# SPIDER_ROBOT.net
KiCad netlist of a schematic drawn in Altium Designer
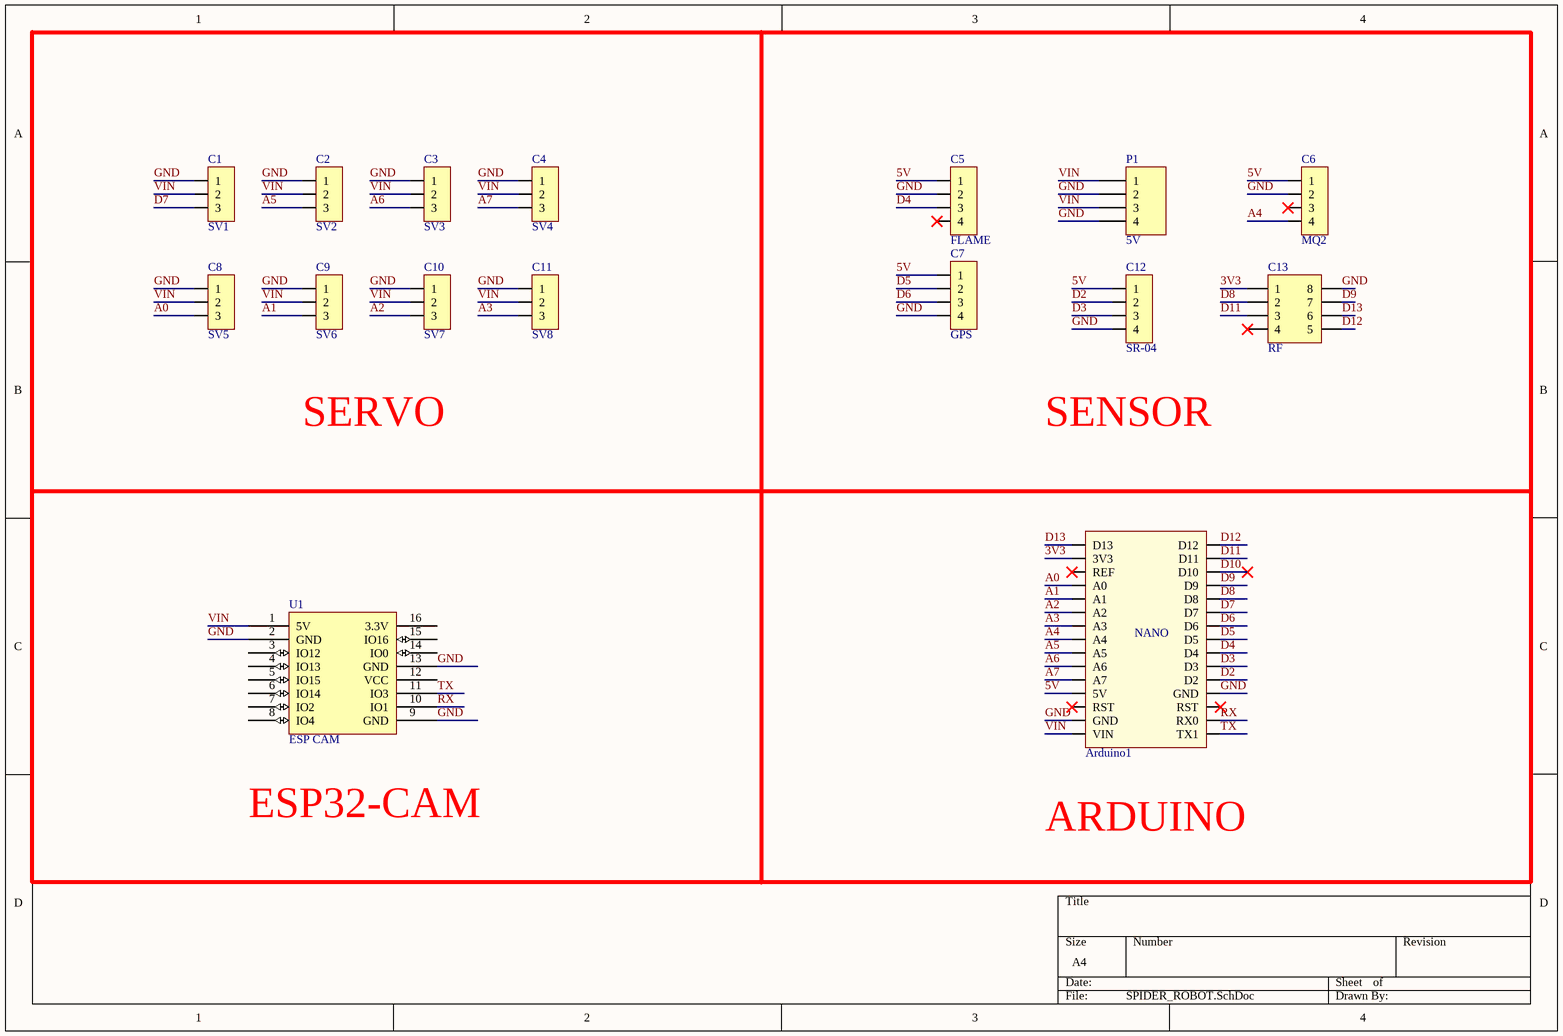
[diagram p0: SPIDER_ROBOT.SchDoc]

(export (version "E")
  (design (tool "Eeschema 10.0.6"))
  (components
    (comp (ref "Arduino1")
      (value "Arduino Nano")
      (footprint "Arduino Nano")
      (description "Arduino NANO")
      (libsource (lib "[Eryson]_Library") (part "Arduino Nano"))
    )
    (comp (ref "C1")
      (value "SV1")
      (footprint "JP3-D1T")
      (description "WR-PHD 2.54 mm Angled Socket Header")
      (fields
        (field (name "MANUFACTURER") "Würth Elektronik eiSos GmbH")
        (field (name "PARTNO") "613003143121")
        (field (name "CREATED BY") "Karrer Zheng")
      )
      (libsource (lib "[Eryson]_Library") (part "JP3"))
    )
    (comp (ref "C2")
      (value "SV2")
      (footprint "JP3-D1T")
      (description "WR-PHD 2.54 mm Angled Socket Header")
      (fields
        (field (name "MANUFACTURER") "Würth Elektronik eiSos GmbH")
        (field (name "PARTNO") "613003143121")
        (field (name "CREATED BY") "Karrer Zheng")
      )
      (libsource (lib "[Eryson]_Library") (part "JP3"))
    )
    (comp (ref "C3")
      (value "SV3")
      (footprint "JP3-D1T")
      (description "WR-PHD 2.54 mm Angled Socket Header")
      (fields
        (field (name "MANUFACTURER") "Würth Elektronik eiSos GmbH")
        (field (name "PARTNO") "613003143121")
        (field (name "CREATED BY") "Karrer Zheng")
      )
      (libsource (lib "[Eryson]_Library") (part "JP3"))
    )
    (comp (ref "C4")
      (value "SV4")
      (footprint "JP3-D1T")
      (description "WR-PHD 2.54 mm Angled Socket Header")
      (fields
        (field (name "MANUFACTURER") "Würth Elektronik eiSos GmbH")
        (field (name "PARTNO") "613003143121")
        (field (name "CREATED BY") "Karrer Zheng")
      )
      (libsource (lib "[Eryson]_Library") (part "JP3"))
    )
    (comp (ref "C5")
      (value "FLAME")
      (footprint "JP4-C1T")
      (description "WR-PHD 2.54 mm Angled Socket Header")
      (fields
        (field (name "MANUFACTURER") "Würth Elektronik eiSos GmbH")
        (field (name "PARTNO") "613004143121")
        (field (name "CREATED BY") "Karrer Zheng")
      )
      (libsource (lib "[Eryson]_Library") (part "JP4"))
    )
    (comp (ref "C6")
      (value "MQ2")
      (footprint "JP4-C1T")
      (description "WR-PHD 2.54 mm Angled Socket Header")
      (fields
        (field (name "MANUFACTURER") "Würth Elektronik eiSos GmbH")
        (field (name "PARTNO") "613004143121")
        (field (name "CREATED BY") "Karrer Zheng")
      )
      (libsource (lib "[Eryson]_Library") (part "JP4"))
    )
    (comp (ref "C7")
      (value "GPS")
      (footprint "JP4-C1T")
      (description "WR-PHD 2.54 mm Angled Socket Header")
      (fields
        (field (name "MANUFACTURER") "Würth Elektronik eiSos GmbH")
        (field (name "PARTNO") "613004143121")
        (field (name "CREATED BY") "Karrer Zheng")
      )
      (libsource (lib "[Eryson]_Library") (part "JP4"))
    )
    (comp (ref "C8")
      (value "SV5")
      (footprint "JP3-D1T")
      (description "WR-PHD 2.54 mm Angled Socket Header")
      (fields
        (field (name "MANUFACTURER") "Würth Elektronik eiSos GmbH")
        (field (name "PARTNO") "613003143121")
        (field (name "CREATED BY") "Karrer Zheng")
      )
      (libsource (lib "[Eryson]_Library") (part "JP3"))
    )
    (comp (ref "C9")
      (value "SV6")
      (footprint "JP3-D1T")
      (description "WR-PHD 2.54 mm Angled Socket Header")
      (fields
        (field (name "MANUFACTURER") "Würth Elektronik eiSos GmbH")
        (field (name "PARTNO") "613003143121")
        (field (name "CREATED BY") "Karrer Zheng")
      )
      (libsource (lib "[Eryson]_Library") (part "JP3"))
    )
    (comp (ref "C10")
      (value "SV7")
      (footprint "JP3-D1T")
      (description "WR-PHD 2.54 mm Angled Socket Header")
      (fields
        (field (name "MANUFACTURER") "Würth Elektronik eiSos GmbH")
        (field (name "PARTNO") "613003143121")
        (field (name "CREATED BY") "Karrer Zheng")
      )
      (libsource (lib "[Eryson]_Library") (part "JP3"))
    )
    (comp (ref "C11")
      (value "SV8")
      (footprint "JP3-D1T")
      (description "WR-PHD 2.54 mm Angled Socket Header")
      (fields
        (field (name "MANUFACTURER") "Würth Elektronik eiSos GmbH")
        (field (name "PARTNO") "613003143121")
        (field (name "CREATED BY") "Karrer Zheng")
      )
      (libsource (lib "[Eryson]_Library") (part "JP3"))
    )
    (comp (ref "C12")
      (value "SR-04")
      (footprint "JP4-C1T")
      (description "WR-PHD 2.54 mm Angled Socket Header")
      (fields
        (field (name "MANUFACTURER") "Würth Elektronik eiSos GmbH")
        (field (name "PARTNO") "613004143121")
        (field (name "CREATED BY") "Karrer Zheng")
      )
      (libsource (lib "[Eryson]_Library") (part "JP4"))
    )
    (comp (ref "C13")
      (value "RF")
      (footprint "JP4-C2T")
      (description "WR-PHD 2.54 mm Dual Socket Header")
      (fields
        (field (name "MANUFACTURER") "Würth Elektronik eiSos GmbH")
        (field (name "PARTNO") "61300821821")
        (field (name "CREATED BY") "Karrer Zheng")
      )
      (libsource (lib "[Eryson]_Library") (part "JP4x2"))
    )
    (comp (ref "P1")
      (value "5V")
      (footprint "DOMINO_4P_2.54MM")
      (libsource (lib "[Eryson]_Library") (part "Domino 4 pin"))
    )
    (comp (ref "U1")
      (value "ESP CAM")
      (footprint "ESP32_CAM")
      (description "ESP-12 Wi-Fi Module by AI-Thinker")
      (libsource (lib "[Eryson]_Library") (part "ESP32_CAM"))
    )
  )
  (nets
    (net (code "1") (name "/3V3") (class "Default")
      (node (ref "Arduino1") (pin "3V3") (pinfunction "3V3_3V3") (pintype "passive"))
      (node (ref "C13") (pin "1") (pinfunction "1_1") (pintype "passive"))
    )
    (net (code "2") (name "/5V") (class "Default")
      (node (ref "Arduino1") (pin "5V") (pinfunction "5V_5V") (pintype "passive"))
      (node (ref "C12") (pin "1") (pinfunction "1_1") (pintype "passive"))
      (node (ref "C5") (pin "1") (pinfunction "1_1") (pintype "passive"))
      (node (ref "C6") (pin "1") (pinfunction "1_1") (pintype "passive"))
      (node (ref "C7") (pin "1") (pinfunction "1_1") (pintype "passive"))
    )
    (net (code "3") (name "/A0") (class "Default")
      (node (ref "Arduino1") (pin "A0") (pinfunction "A0_A0") (pintype "passive"))
      (node (ref "C8") (pin "3") (pinfunction "3_3") (pintype "passive"))
    )
    (net (code "4") (name "/A1") (class "Default")
      (node (ref "Arduino1") (pin "A1") (pinfunction "A1_A1") (pintype "passive"))
      (node (ref "C9") (pin "3") (pinfunction "3_3") (pintype "passive"))
    )
    (net (code "5") (name "/A2") (class "Default")
      (node (ref "Arduino1") (pin "A2") (pinfunction "A2_A2") (pintype "passive"))
      (node (ref "C10") (pin "3") (pinfunction "3_3") (pintype "passive"))
    )
    (net (code "6") (name "/A3") (class "Default")
      (node (ref "Arduino1") (pin "A3") (pinfunction "A3_A3") (pintype "passive"))
      (node (ref "C11") (pin "3") (pinfunction "3_3") (pintype "passive"))
    )
    (net (code "7") (name "/A4") (class "Default")
      (node (ref "Arduino1") (pin "A4") (pinfunction "A4_A4") (pintype "passive"))
      (node (ref "C6") (pin "4") (pinfunction "4_4") (pintype "passive"))
    )
    (net (code "8") (name "/A5") (class "Default")
      (node (ref "Arduino1") (pin "A5") (pinfunction "A5_A5") (pintype "passive"))
      (node (ref "C2") (pin "3") (pinfunction "3_3") (pintype "passive"))
    )
    (net (code "9") (name "/A6") (class "Default")
      (node (ref "Arduino1") (pin "A6") (pinfunction "A6_A6") (pintype "passive"))
      (node (ref "C3") (pin "3") (pinfunction "3_3") (pintype "passive"))
    )
    (net (code "10") (name "/A7") (class "Default")
      (node (ref "Arduino1") (pin "A7") (pinfunction "A7_A7") (pintype "passive"))
      (node (ref "C4") (pin "3") (pinfunction "3_3") (pintype "passive"))
    )
    (net (code "11") (name "/D2") (class "Default")
      (node (ref "Arduino1") (pin "D2") (pinfunction "D2_D2") (pintype "passive"))
      (node (ref "C12") (pin "2") (pinfunction "2_2") (pintype "passive"))
    )
    (net (code "12") (name "/D3") (class "Default")
      (node (ref "Arduino1") (pin "D3") (pinfunction "D3_D3") (pintype "passive"))
      (node (ref "C12") (pin "3") (pinfunction "3_3") (pintype "passive"))
    )
    (net (code "13") (name "/D4") (class "Default")
      (node (ref "Arduino1") (pin "D4") (pinfunction "D4_D4") (pintype "passive"))
      (node (ref "C5") (pin "3") (pinfunction "3_3") (pintype "passive"))
    )
    (net (code "14") (name "/D5") (class "Default")
      (node (ref "Arduino1") (pin "D5") (pinfunction "D5_D5") (pintype "passive"))
      (node (ref "C7") (pin "2") (pinfunction "2_2") (pintype "passive"))
    )
    (net (code "15") (name "/D6") (class "Default")
      (node (ref "Arduino1") (pin "D6") (pinfunction "D6_D6") (pintype "passive"))
      (node (ref "C7") (pin "3") (pinfunction "3_3") (pintype "passive"))
    )
    (net (code "16") (name "/D7") (class "Default")
      (node (ref "Arduino1") (pin "D7") (pinfunction "D7_D7") (pintype "passive"))
      (node (ref "C1") (pin "3") (pinfunction "3_3") (pintype "passive"))
    )
    (net (code "17") (name "/D8") (class "Default")
      (node (ref "Arduino1") (pin "D8") (pinfunction "D8_D8") (pintype "passive"))
      (node (ref "C13") (pin "2") (pinfunction "2_2") (pintype "passive"))
    )
    (net (code "18") (name "/D9") (class "Default")
      (node (ref "Arduino1") (pin "D9") (pinfunction "D9_D9") (pintype "passive"))
      (node (ref "C13") (pin "7") (pinfunction "7_7") (pintype "passive"))
    )
    (net (code "19") (name "/D10") (class "Default")
      (node (ref "Arduino1") (pin "D10") (pinfunction "D10_D10") (pintype "passive+no_connect"))
    )
    (net (code "20") (name "/D11") (class "Default")
      (node (ref "Arduino1") (pin "D11") (pinfunction "D11_D11") (pintype "passive"))
      (node (ref "C13") (pin "3") (pinfunction "3_3") (pintype "passive"))
    )
    (net (code "21") (name "/D12") (class "Default")
      (node (ref "Arduino1") (pin "D12") (pinfunction "D12_D12") (pintype "passive"))
      (node (ref "C13") (pin "5") (pinfunction "5_5") (pintype "passive"))
    )
    (net (code "22") (name "/D13") (class "Default")
      (node (ref "Arduino1") (pin "D13") (pinfunction "D13_D13") (pintype "passive"))
      (node (ref "C13") (pin "6") (pinfunction "6_6") (pintype "passive"))
    )
    (net (code "23") (name "/GND") (class "Default")
      (node (ref "Arduino1") (pin "GND") (pinfunction "GND_GND") (pintype "passive"))
      (node (ref "C1") (pin "1") (pinfunction "1_1") (pintype "passive"))
      (node (ref "C10") (pin "1") (pinfunction "1_1") (pintype "passive"))
      (node (ref "C11") (pin "1") (pinfunction "1_1") (pintype "passive"))
      (node (ref "C12") (pin "4") (pinfunction "4_4") (pintype "passive"))
      (node (ref "C13") (pin "8") (pinfunction "8_8") (pintype "passive"))
      (node (ref "C2") (pin "1") (pinfunction "1_1") (pintype "passive"))
      (node (ref "C3") (pin "1") (pinfunction "1_1") (pintype "passive"))
      (node (ref "C4") (pin "1") (pinfunction "1_1") (pintype "passive"))
      (node (ref "C5") (pin "2") (pinfunction "2_2") (pintype "passive"))
      (node (ref "C6") (pin "2") (pinfunction "2_2") (pintype "passive"))
      (node (ref "C7") (pin "4") (pinfunction "4_4") (pintype "passive"))
      (node (ref "C8") (pin "1") (pinfunction "1_1") (pintype "passive"))
      (node (ref "C9") (pin "1") (pinfunction "1_1") (pintype "passive"))
      (node (ref "P1") (pin "2") (pinfunction "2_2") (pintype "passive"))
      (node (ref "P1") (pin "4") (pinfunction "4_4") (pintype "passive"))
      (node (ref "U1") (pin "13") (pinfunction "GND_13") (pintype "power_in"))
      (node (ref "U1") (pin "2") (pinfunction "GND_2") (pintype "power_in"))
      (node (ref "U1") (pin "9") (pinfunction "GND_9") (pintype "power_in"))
    )
    (net (code "24") (name "/RX") (class "Default")
      (node (ref "Arduino1") (pin "RX0") (pinfunction "RX0_RX0") (pintype "passive"))
      (node (ref "U1") (pin "10") (pinfunction "IO1_10") (pintype "passive"))
    )
    (net (code "25") (name "/TX") (class "Default")
      (node (ref "Arduino1") (pin "TX1") (pinfunction "TX1_TX1") (pintype "passive"))
      (node (ref "U1") (pin "11") (pinfunction "IO3_11") (pintype "passive"))
    )
    (net (code "26") (name "/VIN") (class "Default")
      (node (ref "Arduino1") (pin "VIN") (pinfunction "VIN_VIN") (pintype "passive"))
      (node (ref "C1") (pin "2") (pinfunction "2_2") (pintype "passive"))
      (node (ref "C10") (pin "2") (pinfunction "2_2") (pintype "passive"))
      (node (ref "C11") (pin "2") (pinfunction "2_2") (pintype "passive"))
      (node (ref "C2") (pin "2") (pinfunction "2_2") (pintype "passive"))
      (node (ref "C3") (pin "2") (pinfunction "2_2") (pintype "passive"))
      (node (ref "C4") (pin "2") (pinfunction "2_2") (pintype "passive"))
      (node (ref "C8") (pin "2") (pinfunction "2_2") (pintype "passive"))
      (node (ref "C9") (pin "2") (pinfunction "2_2") (pintype "passive"))
      (node (ref "P1") (pin "1") (pinfunction "1_1") (pintype "passive"))
      (node (ref "P1") (pin "3") (pinfunction "3_3") (pintype "passive"))
      (node (ref "U1") (pin "1") (pinfunction "5V_1") (pintype "power_in"))
    )
    (net (code "27") (name "unconnected-(Arduino1-PadREF)") (class "Default")
      (node (ref "Arduino1") (pin "REF") (pinfunction "REF_REF") (pintype "passive+no_connect"))
    )
    (net (code "28") (name "unconnected-(Arduino1-PadRST)") (class "Default")
      (node (ref "Arduino1") (pin "RST") (pinfunction "RST_RST") (pintype "passive+no_connect"))
    )
    (net (code "29") (name "unconnected-(Arduino1-PadRST)_1") (class "Default")
      (node (ref "Arduino1") (pin "RST") (pinfunction "RST_RST") (pintype "passive+no_connect"))
    )
    (net (code "30") (name "unconnected-(C5-Pad4)") (class "Default")
      (node (ref "C5") (pin "4") (pinfunction "4_4") (pintype "passive+no_connect"))
    )
    (net (code "31") (name "unconnected-(C6-Pad3)") (class "Default")
      (node (ref "C6") (pin "3") (pinfunction "3_3") (pintype "passive+no_connect"))
    )
    (net (code "32") (name "unconnected-(C13-Pad4)") (class "Default")
      (node (ref "C13") (pin "4") (pinfunction "4_4") (pintype "passive+no_connect"))
    )
    (net (code "33") (name "unconnected-(U1-3.3V-Pad16)") (class "Default")
      (node (ref "U1") (pin "16") (pinfunction "3.3V_16") (pintype "power_in"))
    )
    (net (code "34") (name "unconnected-(U1-IO0-Pad14)") (class "Default")
      (node (ref "U1") (pin "14") (pinfunction "IO0_14") (pintype "bidirectional"))
    )
    (net (code "35") (name "unconnected-(U1-IO2-Pad7)") (class "Default")
      (node (ref "U1") (pin "7") (pinfunction "IO2_7") (pintype "bidirectional"))
    )
    (net (code "36") (name "unconnected-(U1-IO4-Pad8)") (class "Default")
      (node (ref "U1") (pin "8") (pinfunction "IO4_8") (pintype "bidirectional"))
    )
    (net (code "37") (name "unconnected-(U1-IO12-Pad3)") (class "Default")
      (node (ref "U1") (pin "3") (pinfunction "IO12_3") (pintype "bidirectional"))
    )
    (net (code "38") (name "unconnected-(U1-IO13-Pad4)") (class "Default")
      (node (ref "U1") (pin "4") (pinfunction "IO13_4") (pintype "bidirectional"))
    )
    (net (code "39") (name "unconnected-(U1-IO14-Pad6)") (class "Default")
      (node (ref "U1") (pin "6") (pinfunction "IO14_6") (pintype "bidirectional"))
    )
    (net (code "40") (name "unconnected-(U1-IO15-Pad5)") (class "Default")
      (node (ref "U1") (pin "5") (pinfunction "IO15_5") (pintype "bidirectional"))
    )
    (net (code "41") (name "unconnected-(U1-IO16-Pad15)") (class "Default")
      (node (ref "U1") (pin "15") (pinfunction "IO16_15") (pintype "bidirectional"))
    )
    (net (code "42") (name "unconnected-(U1-VCC-Pad12)") (class "Default")
      (node (ref "U1") (pin "12") (pinfunction "VCC_12") (pintype "power_in"))
    )
  )
)
